# heater_control.net
KiCad netlist of a schematic drawn in Altium Designer
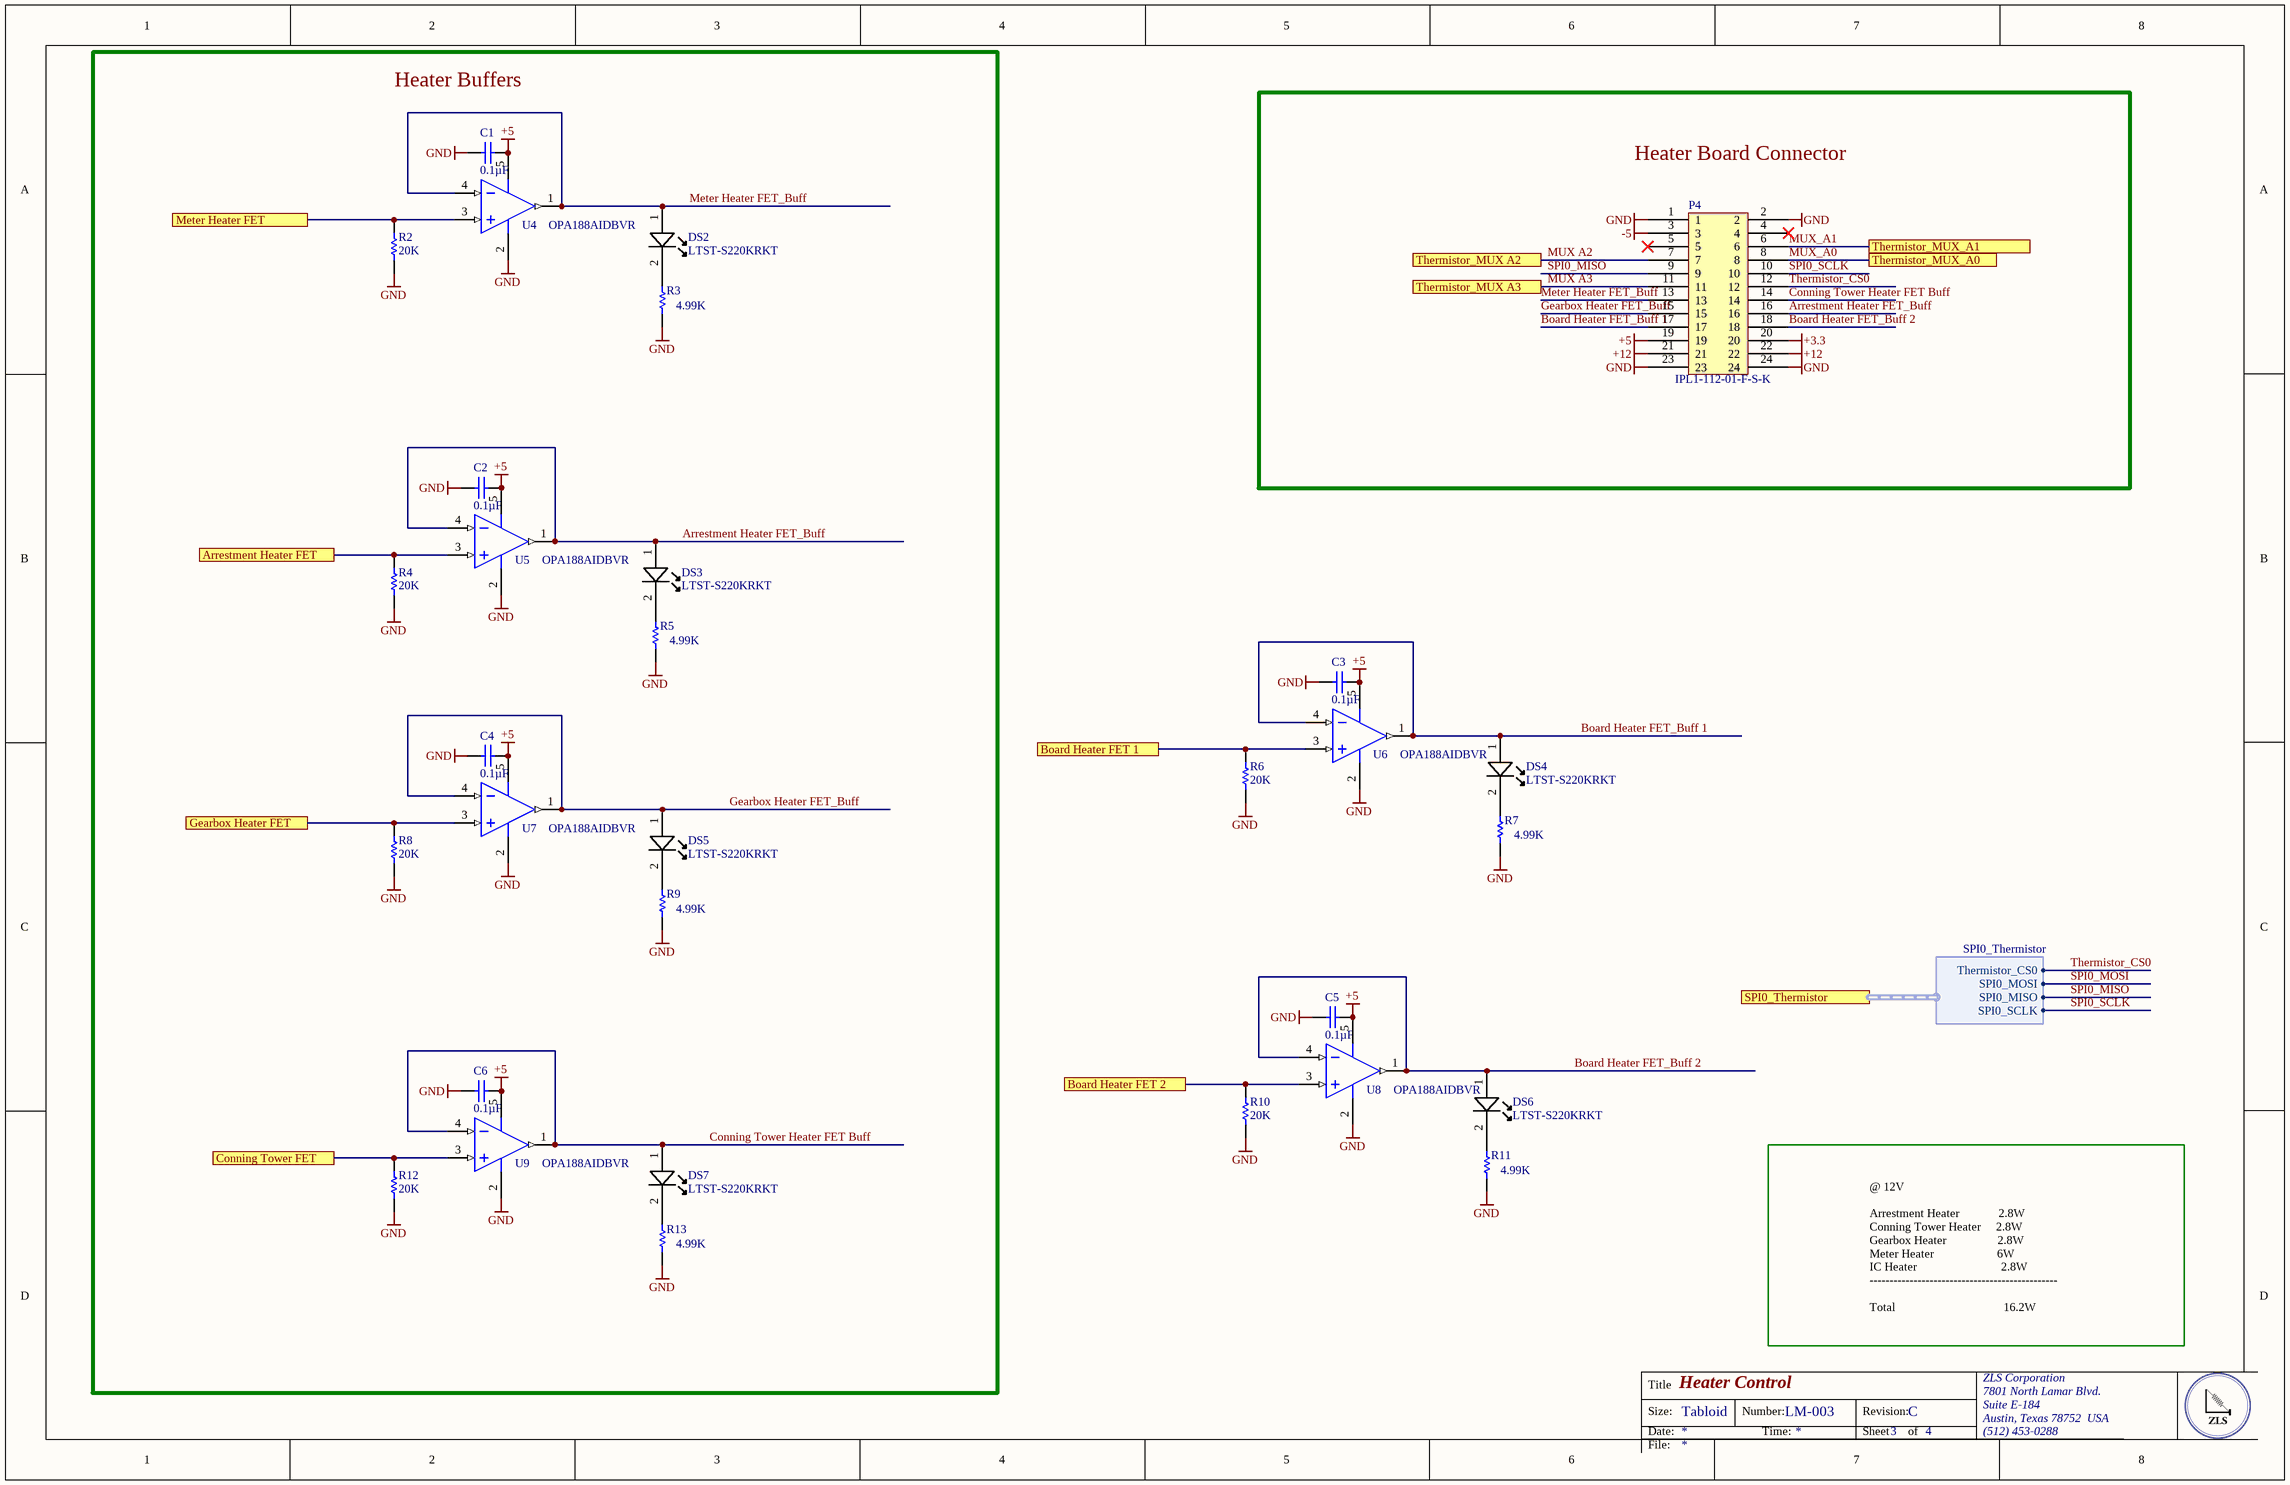
[diagram p0: heater_control.SchDoc]

(export (version "E")
  (design (tool "Eeschema 10.0.6"))
  (components
    (comp (ref "C1")
      (value "CAP CER 0.1UF 25V X7R 0805")
      (footprint "CAPC0805(2012)145_N")
      (fields
        (field (name "MANUFACTURER") "Murata Electronics North America")
        (field (name "MANUFACTURER PART NUMBER") "GRM21BR71E104KA01L")
        (field (name "CAPACITANCE") "0.1µF")
        (field (name "TOLERANCE") "±10%")
      )
      (libsource (lib "Altium Content Vault") (part "CMP-1036-04795-1"))
    )
    (comp (ref "C2")
      (value "CAP CER 0.1UF 25V X7R 0805")
      (footprint "CAPC0805(2012)145_N")
      (fields
        (field (name "MANUFACTURER") "Murata Electronics North America")
        (field (name "MANUFACTURER PART NUMBER") "GRM21BR71E104KA01L")
        (field (name "CAPACITANCE") "0.1µF")
        (field (name "TOLERANCE") "±10%")
      )
      (libsource (lib "Altium Content Vault") (part "CMP-1036-04795-1"))
    )
    (comp (ref "C3")
      (value "CAP CER 0.1UF 25V X7R 0805")
      (footprint "CAPC0805(2012)145_N")
      (fields
        (field (name "MANUFACTURER") "Murata Electronics North America")
        (field (name "MANUFACTURER PART NUMBER") "GRM21BR71E104KA01L")
        (field (name "CAPACITANCE") "0.1µF")
        (field (name "TOLERANCE") "±10%")
      )
      (libsource (lib "Altium Content Vault") (part "CMP-1036-04795-1"))
    )
    (comp (ref "C4")
      (value "CAP CER 0.1UF 25V X7R 0805")
      (footprint "CAPC0805(2012)145_N")
      (fields
        (field (name "MANUFACTURER") "Murata Electronics North America")
        (field (name "MANUFACTURER PART NUMBER") "GRM21BR71E104KA01L")
        (field (name "CAPACITANCE") "0.1µF")
        (field (name "TOLERANCE") "±10%")
      )
      (libsource (lib "Altium Content Vault") (part "CMP-1036-04795-1"))
    )
    (comp (ref "C5")
      (value "CAP CER 0.1UF 25V X7R 0805")
      (footprint "CAPC0805(2012)145_N")
      (fields
        (field (name "MANUFACTURER") "Murata Electronics North America")
        (field (name "MANUFACTURER PART NUMBER") "GRM21BR71E104KA01L")
        (field (name "CAPACITANCE") "0.1µF")
        (field (name "TOLERANCE") "±10%")
      )
      (libsource (lib "Altium Content Vault") (part "CMP-1036-04795-1"))
    )
    (comp (ref "C6")
      (value "CAP CER 0.1UF 25V X7R 0805")
      (footprint "CAPC0805(2012)145_N")
      (fields
        (field (name "MANUFACTURER") "Murata Electronics North America")
        (field (name "MANUFACTURER PART NUMBER") "GRM21BR71E104KA01L")
        (field (name "CAPACITANCE") "0.1µF")
        (field (name "TOLERANCE") "±10%")
      )
      (libsource (lib "Altium Content Vault") (part "CMP-1036-04795-1"))
    )
    (comp (ref "DS2")
      (value "Visible Name Value Type    False Description Lite-On LTST-S220KRKT Red LED, 631 nm 2012 (0805) Side View, Rectangle Lens SMD package STRING")
      (footprint "0805C_L")
      (fields
        (field (name "MANUFACTURER") "Vishay / Lite-On")
        (field (name "MANUFACTURER PART NUMBER") "LTST-S220KRKT")
      )
      (libsource (lib "*") (part "LED A/K"))
    )
    (comp (ref "DS3")
      (value "Visible Name Value Type    False Description Lite-On LTST-S220KRKT Red LED, 631 nm 2012 (0805) Side View, Rectangle Lens SMD package STRING")
      (footprint "0805C_L")
      (fields
        (field (name "MANUFACTURER") "Vishay / Lite-On")
        (field (name "MANUFACTURER PART NUMBER") "LTST-S220KRKT")
      )
      (libsource (lib "*") (part "LED A/K"))
    )
    (comp (ref "DS4")
      (value "Visible Name Value Type    False Description Lite-On LTST-S220KRKT Red LED, 631 nm 2012 (0805) Side View, Rectangle Lens SMD package STRING")
      (footprint "0805C_L")
      (fields
        (field (name "MANUFACTURER") "Vishay / Lite-On")
        (field (name "MANUFACTURER PART NUMBER") "LTST-S220KRKT")
      )
      (libsource (lib "*") (part "LED A/K"))
    )
    (comp (ref "DS5")
      (value "Visible Name Value Type    False Description Lite-On LTST-S220KRKT Red LED, 631 nm 2012 (0805) Side View, Rectangle Lens SMD package STRING")
      (footprint "0805C_L")
      (fields
        (field (name "MANUFACTURER") "Vishay / Lite-On")
        (field (name "MANUFACTURER PART NUMBER") "LTST-S220KRKT")
      )
      (libsource (lib "*") (part "LED A/K"))
    )
    (comp (ref "DS6")
      (value "Visible Name Value Type    False Description Lite-On LTST-S220KRKT Red LED, 631 nm 2012 (0805) Side View, Rectangle Lens SMD package STRING")
      (footprint "0805C_L")
      (fields
        (field (name "MANUFACTURER") "Vishay / Lite-On")
        (field (name "MANUFACTURER PART NUMBER") "LTST-S220KRKT")
      )
      (libsource (lib "*") (part "LED A/K"))
    )
    (comp (ref "DS7")
      (value "Visible Name Value Type    False Description Lite-On LTST-S220KRKT Red LED, 631 nm 2012 (0805) Side View, Rectangle Lens SMD package STRING")
      (footprint "0805C_L")
      (fields
        (field (name "MANUFACTURER") "Vishay / Lite-On")
        (field (name "MANUFACTURER PART NUMBER") "LTST-S220KRKT")
      )
      (libsource (lib "*") (part "LED A/K"))
    )
    (comp (ref "P4")
      (value "IPL1-112-01-F-S-K")
      (footprint "IPL1-112-01-F-S-K")
      (description "IPL1-112-01-F-D-K")
      (fields (field (name "MANUFACTURER") "Samtec Inc."))
      (libsource (lib "ZLS_Schematic_lib") (part "IPL1-112-01-F-S-K"))
    )
    (comp (ref "R2")
      (value "20K")
      (footprint "RESC0805(2012)_L")
      (description "RES SMD 20K OHM 1% 1/8W 0805")
      (fields
        (field (name "MANUFACTURER") "Panasonic Electronic Components")
        (field (name "MANUFACTURER PART NUMBER") "ERJ-6ENF2002V")
      )
      (libsource (lib "Altium Content Vault") (part "CMP-1013-00215-1"))
    )
    (comp (ref "R3")
      (value "4.99K")
      (footprint "RESC0805(2012)_L")
      (description "RES SMD 4.99K OHM 1% 1/8W 0805")
      (fields
        (field (name "MANUFACTURER") "Panasonic Electronic Components")
        (field (name "MANUFACTURER PART NUMBER") "ERJ-6ENF4991V")
      )
      (libsource (lib "Altium Content Vault") (part "CMP-1013-00215-1"))
    )
    (comp (ref "R4")
      (value "20K")
      (footprint "RESC0805(2012)_L")
      (description "RES SMD 20K OHM 1% 1/8W 0805")
      (fields
        (field (name "MANUFACTURER") "Panasonic Electronic Components")
        (field (name "MANUFACTURER PART NUMBER") "ERJ-6ENF2002V")
      )
      (libsource (lib "Altium Content Vault") (part "CMP-1013-00215-1"))
    )
    (comp (ref "R5")
      (value "4.99K")
      (footprint "RESC0805(2012)_L")
      (description "RES SMD 4.99K OHM 1% 1/8W 0805")
      (fields
        (field (name "MANUFACTURER") "Panasonic Electronic Components")
        (field (name "MANUFACTURER PART NUMBER") "ERJ-6ENF4991V")
      )
      (libsource (lib "Altium Content Vault") (part "CMP-1013-00215-1"))
    )
    (comp (ref "R6")
      (value "20K")
      (footprint "RESC0805(2012)_L")
      (description "RES SMD 20K OHM 1% 1/8W 0805")
      (fields
        (field (name "MANUFACTURER") "Panasonic Electronic Components")
        (field (name "MANUFACTURER PART NUMBER") "ERJ-6ENF2002V")
      )
      (libsource (lib "Altium Content Vault") (part "CMP-1013-00215-1"))
    )
    (comp (ref "R7")
      (value "4.99K")
      (footprint "RESC0805(2012)_L")
      (description "RES SMD 4.99K OHM 1% 1/8W 0805")
      (fields
        (field (name "MANUFACTURER") "Panasonic Electronic Components")
        (field (name "MANUFACTURER PART NUMBER") "ERJ-6ENF4991V")
      )
      (libsource (lib "Altium Content Vault") (part "CMP-1013-00215-1"))
    )
    (comp (ref "R8")
      (value "20K")
      (footprint "RESC0805(2012)_L")
      (description "RES SMD 20K OHM 1% 1/8W 0805")
      (fields
        (field (name "MANUFACTURER") "Panasonic Electronic Components")
        (field (name "MANUFACTURER PART NUMBER") "ERJ-6ENF2002V")
      )
      (libsource (lib "Altium Content Vault") (part "CMP-1013-00215-1"))
    )
    (comp (ref "R9")
      (value "4.99K")
      (footprint "RESC0805(2012)_L")
      (description "RES SMD 4.99K OHM 1% 1/8W 0805")
      (fields
        (field (name "MANUFACTURER") "Panasonic Electronic Components")
        (field (name "MANUFACTURER PART NUMBER") "ERJ-6ENF4991V")
      )
      (libsource (lib "Altium Content Vault") (part "CMP-1013-00215-1"))
    )
    (comp (ref "R10")
      (value "20K")
      (footprint "RESC0805(2012)_L")
      (description "RES SMD 20K OHM 1% 1/8W 0805")
      (fields
        (field (name "MANUFACTURER") "Panasonic Electronic Components")
        (field (name "MANUFACTURER PART NUMBER") "ERJ-6ENF2002V")
      )
      (libsource (lib "Altium Content Vault") (part "CMP-1013-00215-1"))
    )
    (comp (ref "R11")
      (value "4.99K")
      (footprint "RESC0805(2012)_L")
      (description "RES SMD 4.99K OHM 1% 1/8W 0805")
      (fields
        (field (name "MANUFACTURER") "Panasonic Electronic Components")
        (field (name "MANUFACTURER PART NUMBER") "ERJ-6ENF4991V")
      )
      (libsource (lib "Altium Content Vault") (part "CMP-1013-00215-1"))
    )
    (comp (ref "R12")
      (value "20K")
      (footprint "RESC0805(2012)_L")
      (description "RES SMD 20K OHM 1% 1/8W 0805")
      (fields
        (field (name "MANUFACTURER") "Panasonic Electronic Components")
        (field (name "MANUFACTURER PART NUMBER") "ERJ-6ENF2002V")
      )
      (libsource (lib "Altium Content Vault") (part "CMP-1013-00215-1"))
    )
    (comp (ref "R13")
      (value "4.99K")
      (footprint "RESC0805(2012)_L")
      (description "RES SMD 4.99K OHM 1% 1/8W 0805")
      (fields
        (field (name "MANUFACTURER") "Panasonic Electronic Components")
        (field (name "MANUFACTURER PART NUMBER") "ERJ-6ENF4991V")
      )
      (libsource (lib "Altium Content Vault") (part "CMP-1013-00215-1"))
    )
    (comp (ref "U4")
      (value "OPA188AIDBVR")
      (footprint "DBV0005A_M")
      (fields (field (name "MANUFACTURER") "Texas Instruments"))
      (libsource (lib "Altium Content Vault") (part "CMP-0809-00005-2"))
    )
    (comp (ref "U5")
      (value "OPA188AIDBVR")
      (footprint "DBV0005A_M")
      (fields (field (name "MANUFACTURER") "Texas Instruments"))
      (libsource (lib "Altium Content Vault") (part "CMP-0809-00005-2"))
    )
    (comp (ref "U6")
      (value "OPA188AIDBVR")
      (footprint "DBV0005A_M")
      (fields (field (name "MANUFACTURER") "Texas Instruments"))
      (libsource (lib "Altium Content Vault") (part "CMP-0809-00005-2"))
    )
    (comp (ref "U7")
      (value "OPA188AIDBVR")
      (footprint "DBV0005A_M")
      (fields (field (name "MANUFACTURER") "Texas Instruments"))
      (libsource (lib "Altium Content Vault") (part "CMP-0809-00005-2"))
    )
    (comp (ref "U8")
      (value "OPA188AIDBVR")
      (footprint "DBV0005A_M")
      (fields (field (name "MANUFACTURER") "Texas Instruments"))
      (libsource (lib "Altium Content Vault") (part "CMP-0809-00005-2"))
    )
    (comp (ref "U9")
      (value "OPA188AIDBVR")
      (footprint "DBV0005A_M")
      (fields (field (name "MANUFACTURER") "Texas Instruments"))
      (libsource (lib "Altium Content Vault") (part "CMP-0809-00005-2"))
    )
  )
  (nets
    (net (code "2") (name "+3.3") (class "Default")
      (node (ref "P4") (pin "20") (pinfunction "20_20") (pintype "passive"))
    )
    (net (code "3") (name "+5") (class "Default")
      (node (ref "C1") (pin "2") (pinfunction "2_2") (pintype "passive"))
      (node (ref "C2") (pin "2") (pinfunction "2_2") (pintype "passive"))
      (node (ref "C3") (pin "2") (pinfunction "2_2") (pintype "passive"))
      (node (ref "C4") (pin "2") (pinfunction "2_2") (pintype "passive"))
      (node (ref "C5") (pin "2") (pinfunction "2_2") (pintype "passive"))
      (node (ref "C6") (pin "2") (pinfunction "2_2") (pintype "passive"))
      (node (ref "P4") (pin "19") (pinfunction "19_19") (pintype "passive"))
      (node (ref "U4") (pin "5") (pinfunction "V+_5") (pintype "power_in"))
      (node (ref "U5") (pin "5") (pinfunction "V+_5") (pintype "power_in"))
      (node (ref "U6") (pin "5") (pinfunction "V+_5") (pintype "power_in"))
      (node (ref "U7") (pin "5") (pinfunction "V+_5") (pintype "power_in"))
      (node (ref "U8") (pin "5") (pinfunction "V+_5") (pintype "power_in"))
      (node (ref "U9") (pin "5") (pinfunction "V+_5") (pintype "power_in"))
    )
    (net (code "4") (name "+12") (class "Default")
      (node (ref "P4") (pin "21") (pinfunction "21_21") (pintype "passive"))
      (node (ref "P4") (pin "22") (pinfunction "22_22") (pintype "passive"))
    )
    (net (code "5") (name "-5") (class "Default")
      (node (ref "P4") (pin "3") (pinfunction "3_3") (pintype "passive"))
    )
    (net (code "6") (name "/Arrestment Heater FET") (class "Default")
      (node (ref "R4") (pin "1") (pinfunction "1_1") (pintype "passive"))
      (node (ref "U5") (pin "3") (pinfunction "IN+_3") (pintype "input"))
    )
    (net (code "7") (name "/Arrestment Heater FET_Buff") (class "Default")
      (node (ref "DS3") (pin "1") (pinfunction "A_1") (pintype "passive"))
      (node (ref "P4") (pin "16") (pinfunction "16_16") (pintype "passive"))
      (node (ref "U5") (pin "1") (pinfunction "OUT_1") (pintype "output"))
      (node (ref "U5") (pin "4") (pinfunction "IN-_4") (pintype "input"))
    )
    (net (code "8") (name "/Board Heater FET 1") (class "Default")
      (node (ref "R6") (pin "1") (pinfunction "1_1") (pintype "passive"))
      (node (ref "U6") (pin "3") (pinfunction "IN+_3") (pintype "input"))
    )
    (net (code "9") (name "/Board Heater FET 2") (class "Default")
      (node (ref "R10") (pin "1") (pinfunction "1_1") (pintype "passive"))
      (node (ref "U8") (pin "3") (pinfunction "IN+_3") (pintype "input"))
    )
    (net (code "10") (name "/Board Heater FET_Buff 1") (class "Default")
      (node (ref "DS4") (pin "1") (pinfunction "A_1") (pintype "passive"))
      (node (ref "P4") (pin "17") (pinfunction "17_17") (pintype "passive"))
      (node (ref "U6") (pin "1") (pinfunction "OUT_1") (pintype "output"))
      (node (ref "U6") (pin "4") (pinfunction "IN-_4") (pintype "input"))
    )
    (net (code "11") (name "/Board Heater FET_Buff 2") (class "Default")
      (node (ref "DS6") (pin "1") (pinfunction "A_1") (pintype "passive"))
      (node (ref "P4") (pin "18") (pinfunction "18_18") (pintype "passive"))
      (node (ref "U8") (pin "1") (pinfunction "OUT_1") (pintype "output"))
      (node (ref "U8") (pin "4") (pinfunction "IN-_4") (pintype "input"))
    )
    (net (code "12") (name "/Conning Tower FET") (class "Default")
      (node (ref "R12") (pin "1") (pinfunction "1_1") (pintype "passive"))
      (node (ref "U9") (pin "3") (pinfunction "IN+_3") (pintype "input"))
    )
    (net (code "13") (name "/Conning Tower Heater FET Buff") (class "Default")
      (node (ref "DS7") (pin "1") (pinfunction "A_1") (pintype "passive"))
      (node (ref "P4") (pin "14") (pinfunction "14_14") (pintype "passive"))
      (node (ref "U9") (pin "1") (pinfunction "OUT_1") (pintype "output"))
      (node (ref "U9") (pin "4") (pinfunction "IN-_4") (pintype "input"))
    )
    (net (code "14") (name "/Gearbox Heater FET") (class "Default")
      (node (ref "R8") (pin "1") (pinfunction "1_1") (pintype "passive"))
      (node (ref "U7") (pin "3") (pinfunction "IN+_3") (pintype "input"))
    )
    (net (code "15") (name "/Gearbox Heater FET_Buff") (class "Default")
      (node (ref "DS5") (pin "1") (pinfunction "A_1") (pintype "passive"))
      (node (ref "P4") (pin "15") (pinfunction "15_15") (pintype "passive"))
      (node (ref "U7") (pin "1") (pinfunction "OUT_1") (pintype "output"))
      (node (ref "U7") (pin "4") (pinfunction "IN-_4") (pintype "input"))
    )
    (net (code "16") (name "/MUX A2") (class "Default")
      (node (ref "P4") (pin "7") (pinfunction "7_7") (pintype "passive"))
    )
    (net (code "17") (name "/MUX A3") (class "Default")
      (node (ref "P4") (pin "11") (pinfunction "11_11") (pintype "passive"))
    )
    (net (code "18") (name "/MUX_A0") (class "Default")
      (node (ref "P4") (pin "8") (pinfunction "8_8") (pintype "passive"))
    )
    (net (code "19") (name "/MUX_A1") (class "Default")
      (node (ref "P4") (pin "6") (pinfunction "6_6") (pintype "passive"))
    )
    (net (code "20") (name "/Meter Heater FET") (class "Default")
      (node (ref "R2") (pin "1") (pinfunction "1_1") (pintype "passive"))
      (node (ref "U4") (pin "3") (pinfunction "IN+_3") (pintype "input"))
    )
    (net (code "21") (name "/Meter Heater FET_Buff") (class "Default")
      (node (ref "DS2") (pin "1") (pinfunction "A_1") (pintype "passive"))
      (node (ref "P4") (pin "13") (pinfunction "13_13") (pintype "passive"))
      (node (ref "U4") (pin "1") (pinfunction "OUT_1") (pintype "output"))
      (node (ref "U4") (pin "4") (pinfunction "IN-_4") (pintype "input"))
    )
    (net (code "22") (name "/SPI0_MISO") (class "Default")
      (node (ref "P4") (pin "9") (pinfunction "9_9") (pintype "passive"))
    )
    (net (code "24") (name "/SPI0_SCLK") (class "Default")
      (node (ref "P4") (pin "10") (pinfunction "10_10") (pintype "passive"))
    )
    (net (code "25") (name "/Thermistor_CS0") (class "Default")
      (node (ref "P4") (pin "12") (pinfunction "12_12") (pintype "passive"))
    )
    (net (code "27") (name "GND") (class "Default")
      (node (ref "C1") (pin "1") (pinfunction "1_1") (pintype "passive"))
      (node (ref "C2") (pin "1") (pinfunction "1_1") (pintype "passive"))
      (node (ref "C3") (pin "1") (pinfunction "1_1") (pintype "passive"))
      (node (ref "C4") (pin "1") (pinfunction "1_1") (pintype "passive"))
      (node (ref "C5") (pin "1") (pinfunction "1_1") (pintype "passive"))
      (node (ref "C6") (pin "1") (pinfunction "1_1") (pintype "passive"))
      (node (ref "P4") (pin "1") (pinfunction "1_1") (pintype "passive"))
      (node (ref "P4") (pin "2") (pinfunction "2_2") (pintype "passive"))
      (node (ref "P4") (pin "23") (pinfunction "23_23") (pintype "passive"))
      (node (ref "P4") (pin "24") (pinfunction "24_24") (pintype "passive"))
      (node (ref "R10") (pin "2") (pinfunction "2_2") (pintype "passive"))
      (node (ref "R11") (pin "2") (pinfunction "2_2") (pintype "passive"))
      (node (ref "R12") (pin "2") (pinfunction "2_2") (pintype "passive"))
      (node (ref "R13") (pin "2") (pinfunction "2_2") (pintype "passive"))
      (node (ref "R2") (pin "2") (pinfunction "2_2") (pintype "passive"))
      (node (ref "R3") (pin "2") (pinfunction "2_2") (pintype "passive"))
      (node (ref "R4") (pin "2") (pinfunction "2_2") (pintype "passive"))
      (node (ref "R5") (pin "2") (pinfunction "2_2") (pintype "passive"))
      (node (ref "R6") (pin "2") (pinfunction "2_2") (pintype "passive"))
      (node (ref "R7") (pin "2") (pinfunction "2_2") (pintype "passive"))
      (node (ref "R8") (pin "2") (pinfunction "2_2") (pintype "passive"))
      (node (ref "R9") (pin "2") (pinfunction "2_2") (pintype "passive"))
      (node (ref "U4") (pin "2") (pinfunction "V-_2") (pintype "power_in"))
      (node (ref "U5") (pin "2") (pinfunction "V-_2") (pintype "power_in"))
      (node (ref "U6") (pin "2") (pinfunction "V-_2") (pintype "power_in"))
      (node (ref "U7") (pin "2") (pinfunction "V-_2") (pintype "power_in"))
      (node (ref "U8") (pin "2") (pinfunction "V-_2") (pintype "power_in"))
      (node (ref "U9") (pin "2") (pinfunction "V-_2") (pintype "power_in"))
    )
    (net (code "28") (name "Net-(DS2-K)") (class "Default")
      (node (ref "DS2") (pin "2") (pinfunction "K_2") (pintype "passive"))
      (node (ref "R3") (pin "1") (pinfunction "1_1") (pintype "passive"))
    )
    (net (code "29") (name "Net-(DS3-K)") (class "Default")
      (node (ref "DS3") (pin "2") (pinfunction "K_2") (pintype "passive"))
      (node (ref "R5") (pin "1") (pinfunction "1_1") (pintype "passive"))
    )
    (net (code "30") (name "Net-(DS4-K)") (class "Default")
      (node (ref "DS4") (pin "2") (pinfunction "K_2") (pintype "passive"))
      (node (ref "R7") (pin "1") (pinfunction "1_1") (pintype "passive"))
    )
    (net (code "31") (name "Net-(DS5-K)") (class "Default")
      (node (ref "DS5") (pin "2") (pinfunction "K_2") (pintype "passive"))
      (node (ref "R9") (pin "1") (pinfunction "1_1") (pintype "passive"))
    )
    (net (code "32") (name "Net-(DS6-K)") (class "Default")
      (node (ref "DS6") (pin "2") (pinfunction "K_2") (pintype "passive"))
      (node (ref "R11") (pin "1") (pinfunction "1_1") (pintype "passive"))
    )
    (net (code "33") (name "Net-(DS7-K)") (class "Default")
      (node (ref "DS7") (pin "2") (pinfunction "K_2") (pintype "passive"))
      (node (ref "R13") (pin "1") (pinfunction "1_1") (pintype "passive"))
    )
    (net (code "34") (name "unconnected-(P4-Pad4)") (class "Default")
      (node (ref "P4") (pin "4") (pinfunction "4_4") (pintype "passive+no_connect"))
    )
    (net (code "35") (name "unconnected-(P4-Pad5)") (class "Default")
      (node (ref "P4") (pin "5") (pinfunction "5_5") (pintype "passive+no_connect"))
    )
  )
)
